# Lulu.net
KiCad netlist of a schematic drawn in EAGLE
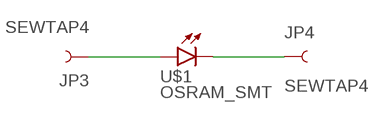
[diagram p0: schematic, sheet 1]

(export (version "E")
  (design (tool "Eeschema 10.0.6"))
  (components
    (comp (ref "JP3")
      (value "SEWTAP4")
      (footprint "eagle-import:PETAL-SMALL")
      (libsource (lib "eagle-import") (part "SEWTAP4"))
    )
    (comp (ref "JP4")
      (value "SEWTAP4")
      (footprint "eagle-import:PETAL-SMALL")
      (libsource (lib "eagle-import") (part "SEWTAP4"))
    )
    (comp (ref "U$1")
      (value "OSRAM_SMT")
      (footprint "eagle-import:OSLON")
      (libsource (lib "eagle-import") (part "OSRAM_SMT"))
    )
  )
  (nets
    (net (code "1") (name "Net-(JP3-Pad1)") (class "Default")
      (node (ref "JP3") (pin "1") (pinfunction "1_1") (pintype "bidirectional"))
      (node (ref "U$1") (pin "A") (pinfunction "A_A") (pintype "power_in"))
    )
    (net (code "2") (name "Net-(JP4-Pad1)") (class "Default")
      (node (ref "JP4") (pin "1") (pinfunction "1_1") (pintype "bidirectional"))
      (node (ref "U$1") (pin "C") (pinfunction "C_C") (pintype "power_in"))
    )
  )
)
